# motherboard_rev0.net
KiCad netlist of a schematic drawn in EAGLE
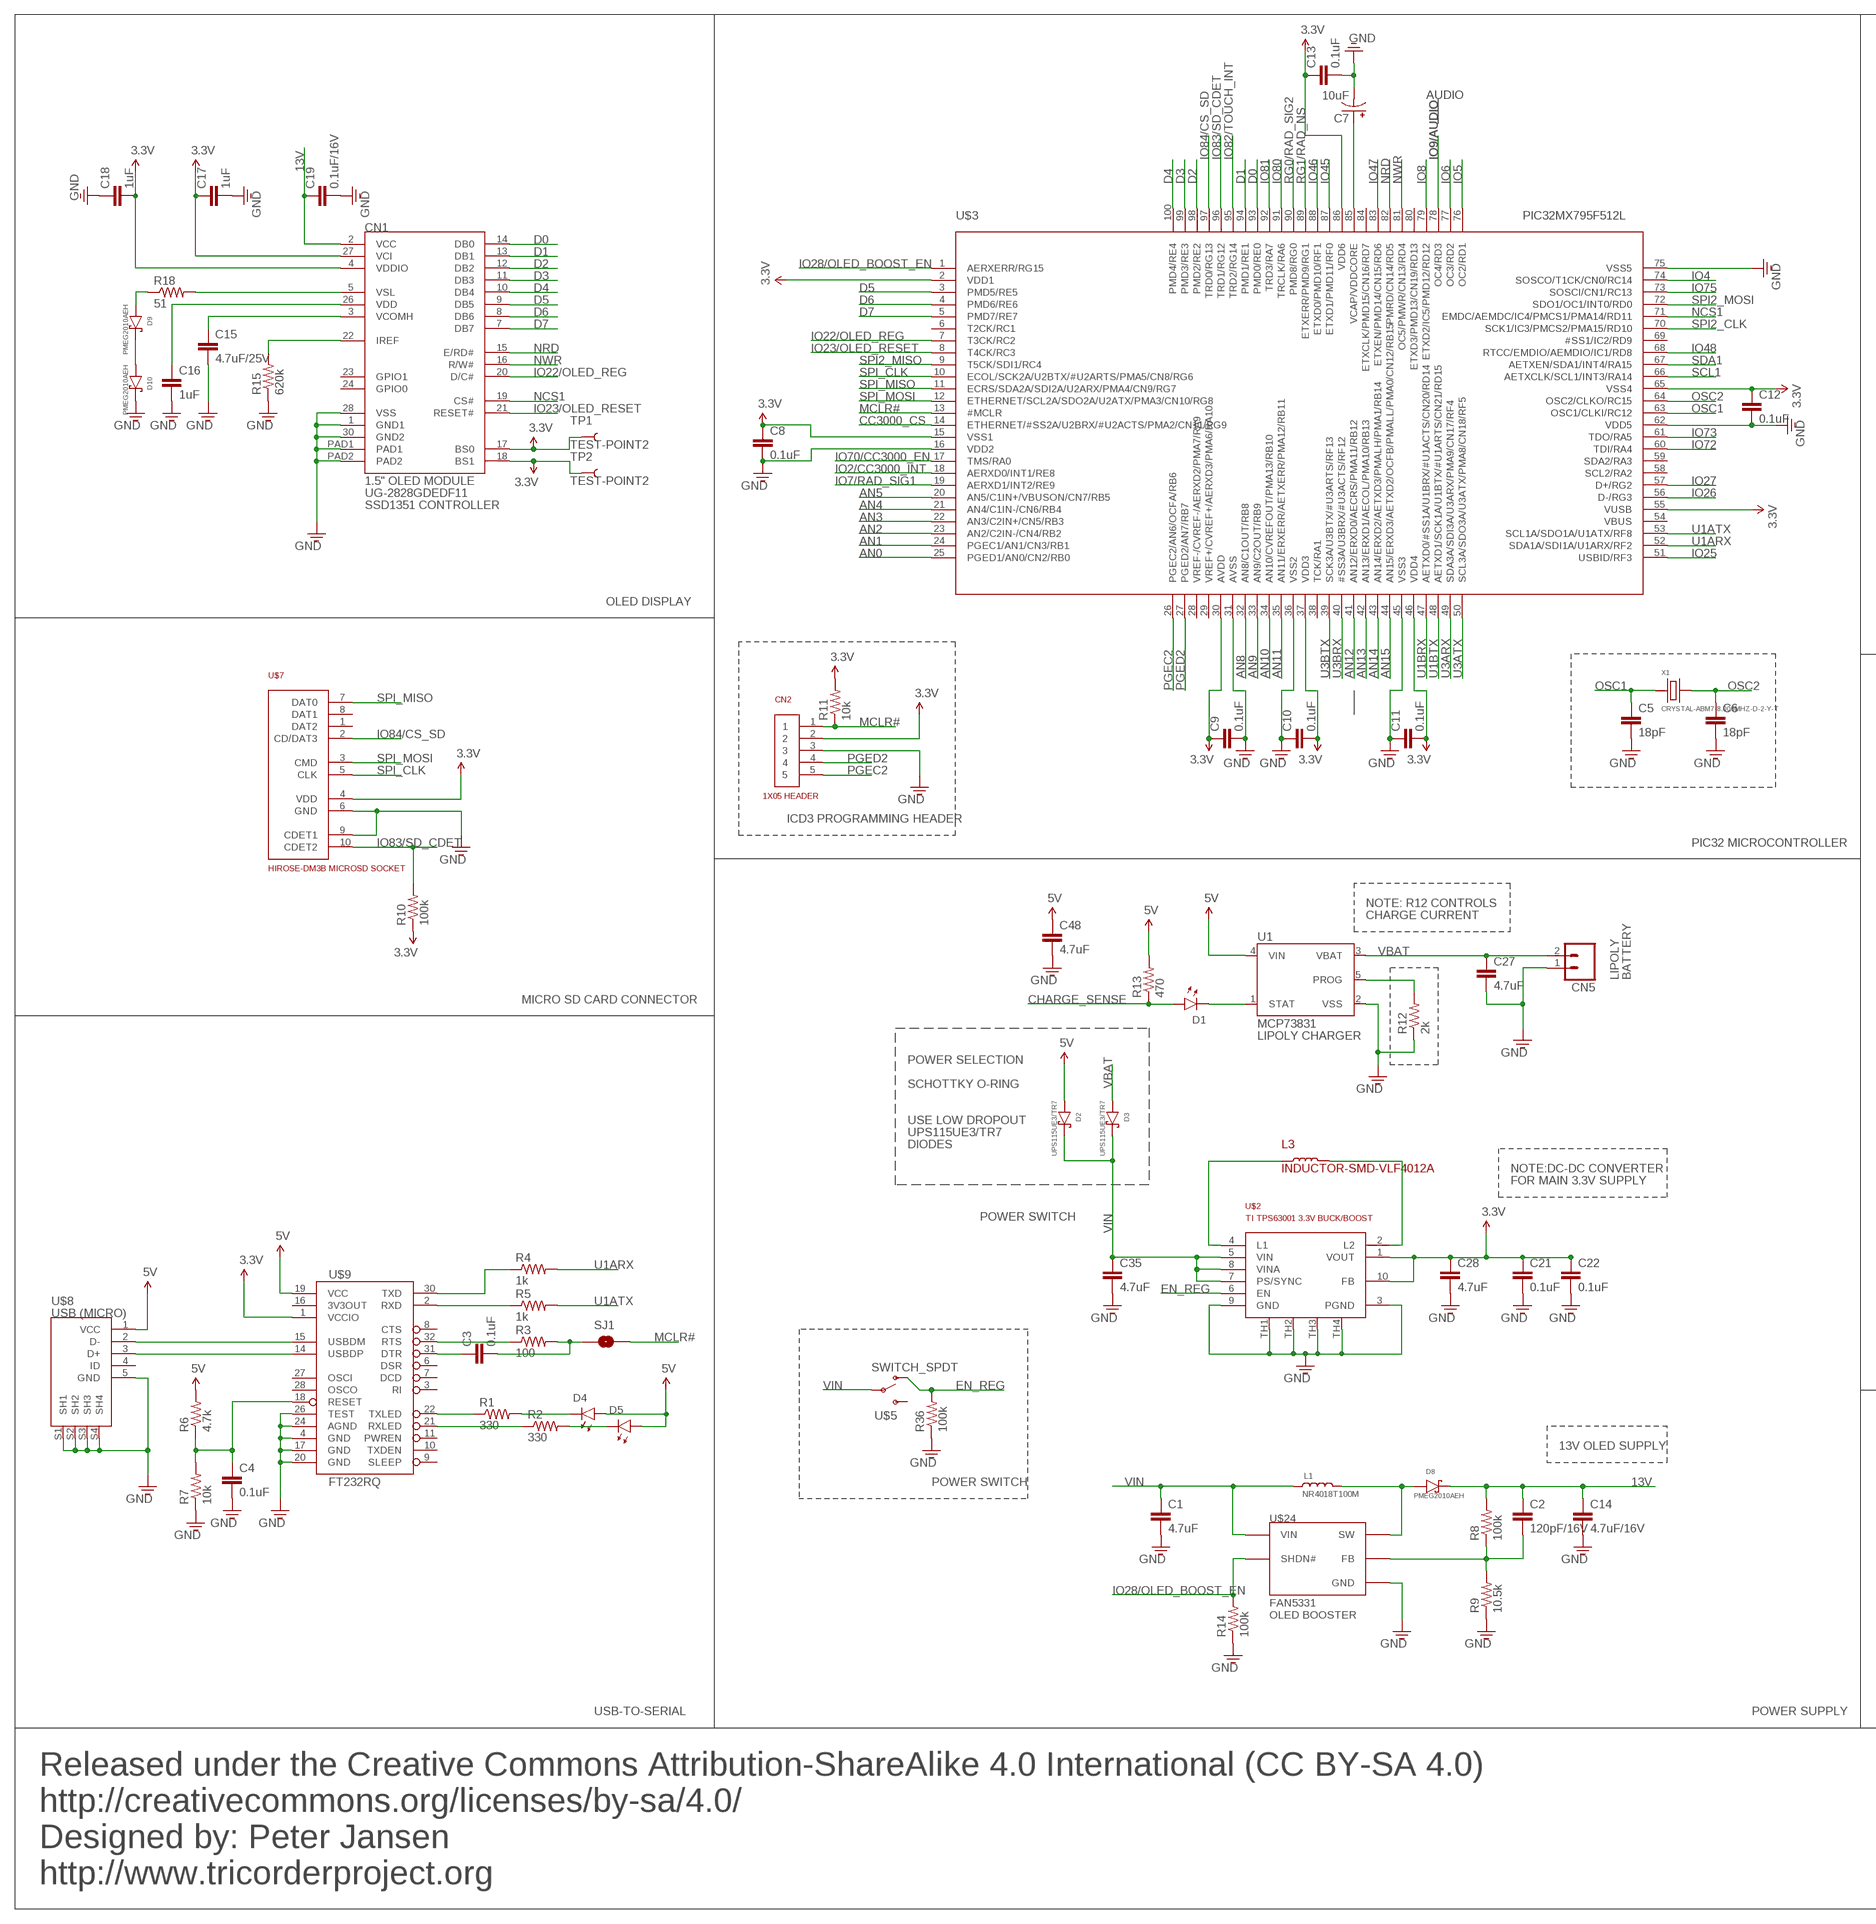
[diagram p0: schematic, sheet 1, part 1 of 2]
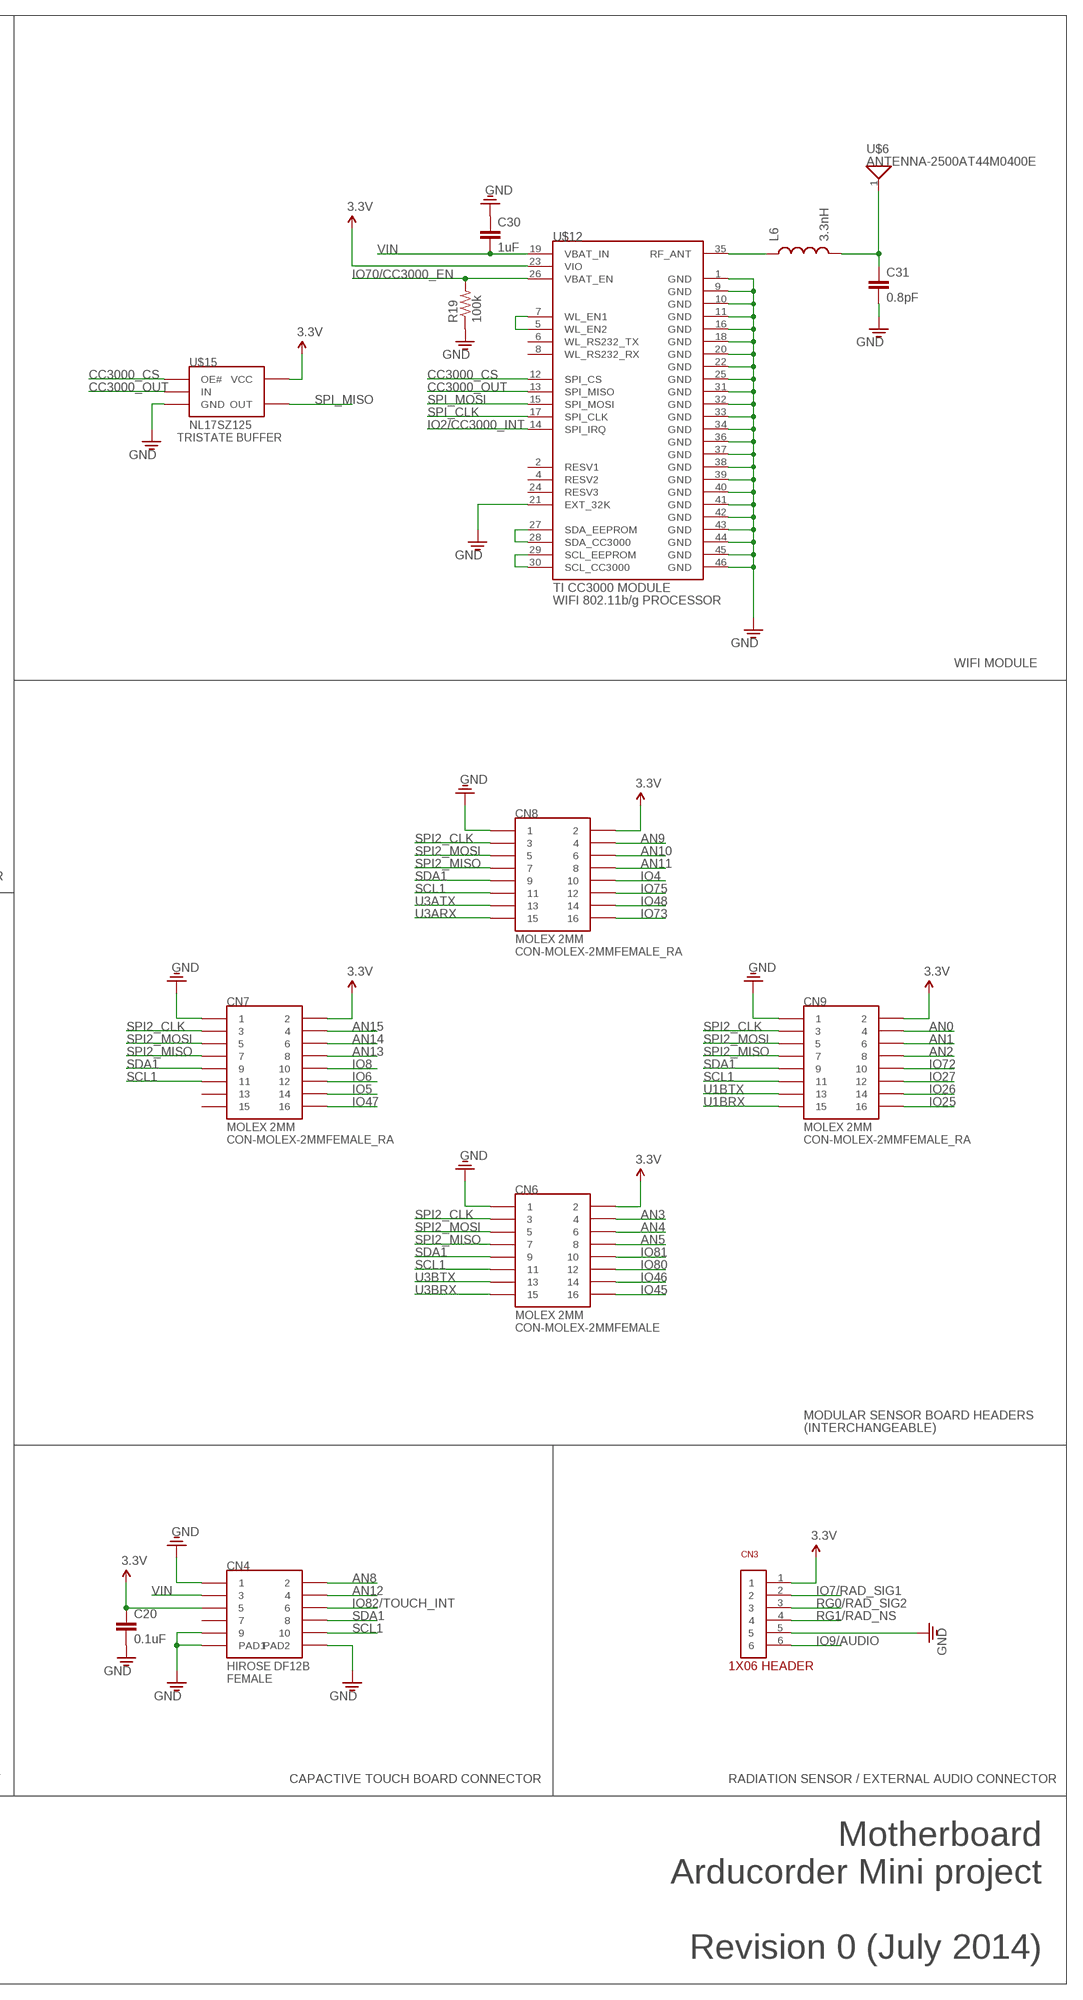
[diagram p1: schematic, sheet 1, part 2 of 2]

(export (version "E")
  (design (tool "Eeschema 10.0.6"))
  (components
    (comp (ref "C1")
      (value "4.7uF")
      (footprint "eagle-import:0603")
      (libsource (lib "eagle-import") (part "CAP0603"))
    )
    (comp (ref "C2")
      (value "120pF/16V")
      (footprint "eagle-import:0603")
      (libsource (lib "eagle-import") (part "notes_mark5a1_CAP0603"))
    )
    (comp (ref "C3")
      (value "0.1uF")
      (footprint "eagle-import:0603")
      (libsource (lib "eagle-import") (part "CAP0603"))
    )
    (comp (ref "C4")
      (value "0.1uF")
      (footprint "eagle-import:0603")
      (libsource (lib "eagle-import") (part "CAP0603"))
    )
    (comp (ref "C5")
      (value "18pF")
      (footprint "eagle-import:0603")
      (libsource (lib "eagle-import") (part "CAP0603"))
    )
    (comp (ref "C6")
      (value "18pF")
      (footprint "eagle-import:0603")
      (libsource (lib "eagle-import") (part "CAP0603"))
    )
    (comp (ref "C7")
      (value "10uF")
      (footprint "eagle-import:EIA3216")
      (libsource (lib "eagle-import") (part "CAP_POL1206"))
    )
    (comp (ref "C8")
      (value "0.1uF")
      (footprint "eagle-import:0603")
      (libsource (lib "eagle-import") (part "CAP0603"))
    )
    (comp (ref "C9")
      (value "0.1uF")
      (footprint "eagle-import:0603")
      (libsource (lib "eagle-import") (part "CAP0603"))
    )
    (comp (ref "C10")
      (value "0.1uF")
      (footprint "eagle-import:0603")
      (libsource (lib "eagle-import") (part "CAP0603"))
    )
    (comp (ref "C11")
      (value "0.1uF")
      (footprint "eagle-import:0603")
      (libsource (lib "eagle-import") (part "CAP0603"))
    )
    (comp (ref "C12")
      (value "0.1uF")
      (footprint "eagle-import:0603")
      (libsource (lib "eagle-import") (part "CAP0603"))
    )
    (comp (ref "C13")
      (value "0.1uF")
      (footprint "eagle-import:0603")
      (libsource (lib "eagle-import") (part "CAP0603"))
    )
    (comp (ref "C14")
      (value "4.7uF/16V")
      (footprint "eagle-import:0603")
      (libsource (lib "eagle-import") (part "CAP0603"))
    )
    (comp (ref "C15")
      (value "4.7uF/25V")
      (footprint "eagle-import:0603")
      (libsource (lib "eagle-import") (part "CAP0603"))
    )
    (comp (ref "C16")
      (value "1uF")
      (footprint "eagle-import:0603")
      (libsource (lib "eagle-import") (part "CAP0603"))
    )
    (comp (ref "C17")
      (value "1uF")
      (footprint "eagle-import:0603")
      (libsource (lib "eagle-import") (part "CAP0603"))
    )
    (comp (ref "C18")
      (value "1uF")
      (footprint "eagle-import:0603")
      (libsource (lib "eagle-import") (part "CAP0603"))
    )
    (comp (ref "C19")
      (value "0.1uF/16V")
      (footprint "eagle-import:0603")
      (libsource (lib "eagle-import") (part "CAP0603"))
    )
    (comp (ref "C20")
      (value "0.1uF")
      (footprint "eagle-import:0603")
      (libsource (lib "eagle-import") (part "CAP0603"))
    )
    (comp (ref "C21")
      (value "0.1uF")
      (footprint "eagle-import:0603")
      (libsource (lib "eagle-import") (part "CAP0603"))
    )
    (comp (ref "C22")
      (value "0.1uF")
      (footprint "eagle-import:0603")
      (libsource (lib "eagle-import") (part "CAP0603"))
    )
    (comp (ref "C27")
      (value "4.7uF")
      (footprint "eagle-import:0603")
      (libsource (lib "eagle-import") (part "CAP0603"))
    )
    (comp (ref "C28")
      (value "4.7uF")
      (footprint "eagle-import:0603")
      (libsource (lib "eagle-import") (part "CAP0603"))
    )
    (comp (ref "C30")
      (value "1uF")
      (footprint "eagle-import:0603")
      (libsource (lib "eagle-import") (part "CAP0603"))
    )
    (comp (ref "C31")
      (value "0.8pF")
      (footprint "eagle-import:C0402")
      (libsource (lib "eagle-import") (part "CAP0402"))
    )
    (comp (ref "C35")
      (value "4.7uF")
      (footprint "eagle-import:0603")
      (libsource (lib "eagle-import") (part "CAP0603"))
    )
    (comp (ref "C48")
      (value "4.7uF")
      (footprint "eagle-import:0603")
      (libsource (lib "eagle-import") (part "CAP0603"))
    )
    (comp (ref "CN1")
      (value "UG-2828GDEDF11-1.5OLED")
      (footprint "eagle-import:XF2M-3015-1A-1.5LCD")
      (libsource (lib "eagle-import") (part "UG-2828GDEDF11-1.5OLED"))
    )
    (comp (ref "CN2")
      (value "1X05")
      (footprint "eagle-import:1X05")
      (libsource (lib "eagle-import") (part "1X05"))
    )
    (comp (ref "CN3")
      (value "1X06")
      (footprint "eagle-import:1X06")
      (libsource (lib "eagle-import") (part "1X06"))
    )
    (comp (ref "CN4")
      (value "FEMALE")
      (footprint "eagle-import:DF12B(3.0)-10DP-0.5V(86)")
      (libsource (lib "eagle-import") (part "CON-HIROSE-DF12FEMALE"))
    )
    (comp (ref "CN5")
      (value "M02-JST-2MM-SMT")
      (footprint "eagle-import:JST-2-SMD")
      (libsource (lib "eagle-import") (part "M02-JST-2MM-SMT"))
    )
    (comp (ref "CN6")
      (value "CON-MOLEX-2MMFEMALE")
      (footprint "eagle-import:MOLEX-0791091007")
      (libsource (lib "eagle-import") (part "CON-MOLEX-2MMFEMALE"))
    )
    (comp (ref "CN7")
      (value "CON-MOLEX-2MMFEMALE_RA")
      (footprint "eagle-import:MOLEX-87368-1624")
      (libsource (lib "eagle-import") (part "CON-MOLEX-2MMFEMALE_RA"))
    )
    (comp (ref "CN8")
      (value "CON-MOLEX-2MMFEMALE_RA")
      (footprint "eagle-import:MOLEX-87368-1624")
      (libsource (lib "eagle-import") (part "CON-MOLEX-2MMFEMALE_RA"))
    )
    (comp (ref "CN9")
      (value "CON-MOLEX-2MMFEMALE_RA")
      (footprint "eagle-import:MOLEX-87368-1624")
      (libsource (lib "eagle-import") (part "CON-MOLEX-2MMFEMALE_RA"))
    )
    (comp (ref "D1")
      (value "0605-LED")
      (footprint "eagle-import:0603-LED")
      (libsource (lib "eagle-import") (part "0605-LED"))
    )
    (comp (ref "D2")
      (value "UPS115UE3/TR7")
      (footprint "eagle-import:DO-214BA")
      (libsource (lib "eagle-import") (part "DIODE-SCHOTTKY"))
    )
    (comp (ref "D3")
      (value "UPS115UE3/TR7")
      (footprint "eagle-import:DO-214BA")
      (libsource (lib "eagle-import") (part "DIODE-SCHOTTKY"))
    )
    (comp (ref "D4")
      (value "0605-LED")
      (footprint "eagle-import:0603-LED")
      (libsource (lib "eagle-import") (part "0605-LED"))
    )
    (comp (ref "D5")
      (value "0605-LED")
      (footprint "eagle-import:0603-LED")
      (libsource (lib "eagle-import") (part "0605-LED"))
    )
    (comp (ref "D8")
      (value "PMEG2010AEH")
      (footprint "eagle-import:SOD123F")
      (libsource (lib "eagle-import") (part "DIODE-SCHOTTKYSOD123F"))
    )
    (comp (ref "D9")
      (value "PMEG2010AEH")
      (footprint "eagle-import:SOD123F")
      (libsource (lib "eagle-import") (part "DIODE-SCHOTTKYSOD123F"))
    )
    (comp (ref "D10")
      (value "PMEG2010AEH")
      (footprint "eagle-import:SOD123F")
      (libsource (lib "eagle-import") (part "DIODE-SCHOTTKYSOD123F"))
    )
    (comp (ref "L1")
      (value "NR4018T100M")
      (footprint "eagle-import:NR4018T100M")
      (libsource (lib "eagle-import") (part "INDUCTORNR4018T100M"))
    )
    (comp (ref "L3")
      (value "INDUCTOR-SMD-VLF4012A")
      (footprint "eagle-import:VLF4012A")
      (libsource (lib "eagle-import") (part "INDUCTOR-SMD-VLF4012A"))
    )
    (comp (ref "L6")
      (value "3.3nH")
      (footprint "eagle-import:C0402")
      (libsource (lib "eagle-import") (part "INDUCTOR0402"))
    )
    (comp (ref "R1")
      (value "330")
      (footprint "eagle-import:0603")
      (libsource (lib "eagle-import") (part "RESISTOR0603"))
    )
    (comp (ref "R2")
      (value "330")
      (footprint "eagle-import:0603")
      (libsource (lib "eagle-import") (part "RESISTOR0603"))
    )
    (comp (ref "R3")
      (value "100")
      (footprint "eagle-import:0603")
      (libsource (lib "eagle-import") (part "RESISTOR0603"))
    )
    (comp (ref "R4")
      (value "1k")
      (footprint "eagle-import:0603")
      (libsource (lib "eagle-import") (part "RESISTOR0603"))
    )
    (comp (ref "R5")
      (value "1k")
      (footprint "eagle-import:0603")
      (libsource (lib "eagle-import") (part "RESISTOR0603"))
    )
    (comp (ref "R6")
      (value "4.7k")
      (footprint "eagle-import:0603")
      (libsource (lib "eagle-import") (part "RESISTOR0603"))
    )
    (comp (ref "R7")
      (value "10k")
      (footprint "eagle-import:0603")
      (libsource (lib "eagle-import") (part "RESISTOR0603"))
    )
    (comp (ref "R8")
      (value "100k")
      (footprint "eagle-import:0603")
      (libsource (lib "eagle-import") (part "notes_mark5a1_RESISTOR0603"))
    )
    (comp (ref "R9")
      (value "10.5k")
      (footprint "eagle-import:0603")
      (libsource (lib "eagle-import") (part "notes_mark5a1_RESISTOR0603"))
    )
    (comp (ref "R10")
      (value "100k")
      (footprint "eagle-import:0603")
      (libsource (lib "eagle-import") (part "RESISTOR0603"))
    )
    (comp (ref "R11")
      (value "10k")
      (footprint "eagle-import:0603")
      (libsource (lib "eagle-import") (part "RESISTOR0603"))
    )
    (comp (ref "R12")
      (value "2k")
      (footprint "eagle-import:0603")
      (libsource (lib "eagle-import") (part "RESISTOR0603"))
    )
    (comp (ref "R13")
      (value "470")
      (footprint "eagle-import:0603")
      (libsource (lib "eagle-import") (part "RESISTOR0603"))
    )
    (comp (ref "R14")
      (value "100k")
      (footprint "eagle-import:0603")
      (libsource (lib "eagle-import") (part "notes_mark5a1_RESISTOR0603"))
    )
    (comp (ref "R15")
      (value "620k")
      (footprint "eagle-import:0603")
      (libsource (lib "eagle-import") (part "notes_mark5a1_RESISTOR0603"))
    )
    (comp (ref "R18")
      (value "51")
      (footprint "eagle-import:0603")
      (libsource (lib "eagle-import") (part "notes_mark5a1_RESISTOR0603"))
    )
    (comp (ref "R19")
      (value "100k")
      (footprint "eagle-import:0603")
      (libsource (lib "eagle-import") (part "notes_mark5a1_RESISTOR0603"))
    )
    (comp (ref "R36")
      (value "100k")
      (footprint "eagle-import:0603")
      (libsource (lib "eagle-import") (part "RESISTOR0603"))
    )
    (comp (ref "SJ1")
      (value "SOLDERJUMPERTRACE")
      (footprint "eagle-import:SJ_2S-TRACE")
      (libsource (lib "eagle-import") (part "SOLDERJUMPERTRACE"))
    )
    (comp (ref "TP1")
      (value "TEST-POINT2")
      (footprint "eagle-import:PAD.02X.02")
      (libsource (lib "eagle-import") (part "TEST-POINT2"))
    )
    (comp (ref "TP2")
      (value "TEST-POINT2")
      (footprint "eagle-import:PAD.02X.02")
      (libsource (lib "eagle-import") (part "TEST-POINT2"))
    )
    (comp (ref "U$2")
      (value "TI-TPS63001-3.3V-BUCKBOOST")
      (footprint "eagle-import:TPS63001")
      (libsource (lib "eagle-import") (part "TI-TPS63001-3.3V-BUCKBOOST"))
    )
    (comp (ref "U$3")
      (value "PIC32MX795F512L-80I/PF")
      (footprint "eagle-import:SQFP-S-14X14-100")
      (libsource (lib "eagle-import") (part "PIC32MX795F512L-80I/PF"))
    )
    (comp (ref "U$5")
      (value "SWITCH_SPDT")
      (footprint "eagle-import:KPS-1290")
      (libsource (lib "eagle-import") (part "SWITCH_SPDT"))
    )
    (comp (ref "U$6")
      (value "ANTENNA-2500AT44M0400E")
      (footprint "eagle-import:ANT-2500AT44M0400E")
      (libsource (lib "eagle-import") (part "ANTENNA-2500AT44M0400E"))
    )
    (comp (ref "U$7")
      (value "CON-HIROSE-DM3B-MICROSD")
      (footprint "eagle-import:CON-HIROSE-DM3B-MICROSD")
      (libsource (lib "eagle-import") (part "CON-HIROSE-DM3B-MICROSD"))
    )
    (comp (ref "U$8")
      (value "USB-MICROB")
      (footprint "eagle-import:FCI-10104110-0001LF")
      (libsource (lib "eagle-import") (part "USB-MICROB"))
    )
    (comp (ref "U$9")
      (value "FT232RQ")
      (footprint "eagle-import:QFN-32")
      (libsource (lib "eagle-import") (part "FT232RQ"))
    )
    (comp (ref "U$12")
      (value "CC3000")
      (footprint "eagle-import:CC3000")
      (libsource (lib "eagle-import") (part "CC3000"))
    )
    (comp (ref "U$15")
      (value "BUFFER-NL17SZ125")
      (footprint "eagle-import:TSOP-5")
      (libsource (lib "eagle-import") (part "BUFFER-NL17SZ125"))
    )
    (comp (ref "U$24")
      (value "FAN5331-BOOST")
      (footprint "eagle-import:TSOP-5")
      (libsource (lib "eagle-import") (part "FAN5331-BOOST"))
    )
    (comp (ref "U1")
      (value "MCP73831")
      (footprint "eagle-import:SOT23-5")
      (libsource (lib "eagle-import") (part "MCP73831"))
    )
    (comp (ref "X1")
      (value "CRYSTAL-ABM7-8.000MHZ-D-2-Y-T")
      (footprint "eagle-import:CYRSTAL-6.0X3.5MM")
      (libsource (lib "eagle-import") (part "CRYSTAL-ABM7-8.000MHZ-D-2-Y-T"))
    )
  )
  (nets
    (net (code "1") (name "/13V") (class "Default")
      (node (ref "C14") (pin "1") (pinfunction "1_1") (pintype "passive"))
      (node (ref "C19") (pin "1") (pinfunction "1_1") (pintype "passive"))
      (node (ref "C2") (pin "1") (pinfunction "1_1") (pintype "passive"))
      (node (ref "CN1") (pin "2") (pinfunction "VCC_2") (pintype "bidirectional"))
      (node (ref "D8") (pin "1") (pinfunction "CATHODE_1") (pintype "bidirectional"))
      (node (ref "R8") (pin "2") (pinfunction "2_2") (pintype "passive"))
    )
    (net (code "2") (name "/AN0") (class "Default")
      (node (ref "CN9") (pin "4") (pinfunction "4_4") (pintype "bidirectional"))
      (node (ref "U$3") (pin "25") (pinfunction "PGED1/AN0/CN2/RB0_25") (pintype "bidirectional"))
    )
    (net (code "3") (name "/AN1") (class "Default")
      (node (ref "CN9") (pin "6") (pinfunction "6_6") (pintype "bidirectional"))
      (node (ref "U$3") (pin "24") (pinfunction "PGEC1/AN1/CN3/RB1_24") (pintype "bidirectional"))
    )
    (net (code "4") (name "/AN2") (class "Default")
      (node (ref "CN9") (pin "8") (pinfunction "8_8") (pintype "bidirectional"))
      (node (ref "U$3") (pin "23") (pinfunction "AN2/C2IN-/CN4/RB2_23") (pintype "bidirectional"))
    )
    (net (code "5") (name "/AN3") (class "Default")
      (node (ref "CN6") (pin "4") (pinfunction "4_4") (pintype "bidirectional"))
      (node (ref "U$3") (pin "22") (pinfunction "AN3/C2IN+/CN5/RB3_22") (pintype "bidirectional"))
    )
    (net (code "6") (name "/AN4") (class "Default")
      (node (ref "CN6") (pin "6") (pinfunction "6_6") (pintype "bidirectional"))
      (node (ref "U$3") (pin "21") (pinfunction "AN4/C1IN-/CN6/RB4_21") (pintype "bidirectional"))
    )
    (net (code "7") (name "/AN5") (class "Default")
      (node (ref "CN6") (pin "8") (pinfunction "8_8") (pintype "bidirectional"))
      (node (ref "U$3") (pin "20") (pinfunction "AN5/C1IN+/VBUSON/CN7/RB5_20") (pintype "bidirectional"))
    )
    (net (code "8") (name "/AN8") (class "Default")
      (node (ref "CN4") (pin "2") (pinfunction "2_2") (pintype "bidirectional"))
      (node (ref "U$3") (pin "32") (pinfunction "AN8/C1OUT/RB8_32") (pintype "bidirectional"))
    )
    (net (code "9") (name "/AN9") (class "Default")
      (node (ref "CN8") (pin "4") (pinfunction "4_4") (pintype "bidirectional"))
      (node (ref "U$3") (pin "33") (pinfunction "AN9/C2OUT/RB9_33") (pintype "bidirectional"))
    )
    (net (code "10") (name "/AN10") (class "Default")
      (node (ref "CN8") (pin "6") (pinfunction "6_6") (pintype "bidirectional"))
      (node (ref "U$3") (pin "34") (pinfunction "AN10/CVREFOUT/PMA13/RB10_34") (pintype "bidirectional"))
    )
    (net (code "11") (name "/AN11") (class "Default")
      (node (ref "CN8") (pin "8") (pinfunction "8_8") (pintype "bidirectional"))
      (node (ref "U$3") (pin "35") (pinfunction "AN11/ERXERR/AETXERR/PMA12/RB11_35") (pintype "bidirectional"))
    )
    (net (code "12") (name "/AN12") (class "Default")
      (node (ref "CN4") (pin "4") (pinfunction "4_4") (pintype "bidirectional"))
      (node (ref "U$3") (pin "41") (pinfunction "AN12/ERXD0/AECRS/PMA11/RB12_41") (pintype "bidirectional"))
    )
    (net (code "13") (name "/AN13") (class "Default")
      (node (ref "CN7") (pin "8") (pinfunction "8_8") (pintype "bidirectional"))
      (node (ref "U$3") (pin "42") (pinfunction "AN13/ERXD1/AECOL/PMA10/RB13_42") (pintype "bidirectional"))
    )
    (net (code "14") (name "/AN14") (class "Default")
      (node (ref "CN7") (pin "6") (pinfunction "6_6") (pintype "bidirectional"))
      (node (ref "U$3") (pin "43") (pinfunction "AN14/ERXD2/AETXD3/PMALH/PMA1/RB14_43") (pintype "bidirectional"))
    )
    (net (code "15") (name "/AN15") (class "Default")
      (node (ref "CN7") (pin "4") (pinfunction "4_4") (pintype "bidirectional"))
      (node (ref "U$3") (pin "44") (pinfunction "AN15/ERXD3/AETXD2/OCFB/PMALL/PMA0/CN12/RB15_44") (pintype "bidirectional"))
    )
    (net (code "16") (name "/CC3000_CS") (class "Default")
      (node (ref "U$12") (pin "12") (pinfunction "SPI_CS_12") (pintype "bidirectional"))
      (node (ref "U$15") (pin "1") (pinfunction "OE#_1") (pintype "bidirectional"))
      (node (ref "U$3") (pin "14") (pinfunction "ETHERNET/#SS2A/U2BRX/#U2ACTS/PMA2/CN11/RG9_14") (pintype "bidirectional"))
    )
    (net (code "17") (name "/CC3000_OUT") (class "Default")
      (node (ref "U$12") (pin "13") (pinfunction "SPI_MISO_13") (pintype "bidirectional"))
      (node (ref "U$15") (pin "2") (pinfunction "IN_2") (pintype "bidirectional"))
    )
    (net (code "18") (name "/CHARGE_SENSE") (class "Default")
      (node (ref "D1") (pin "ANODE") (pinfunction "ANODE_ANODE") (pintype "bidirectional"))
      (node (ref "R13") (pin "1") (pinfunction "1_1") (pintype "passive"))
    )
    (net (code "19") (name "/D0") (class "Default")
      (node (ref "CN1") (pin "14") (pinfunction "DB0_14") (pintype "bidirectional"))
      (node (ref "U$3") (pin "93") (pinfunction "PMD0/RE0_93") (pintype "bidirectional"))
    )
    (net (code "20") (name "/D1") (class "Default")
      (node (ref "CN1") (pin "13") (pinfunction "DB1_13") (pintype "bidirectional"))
      (node (ref "U$3") (pin "94") (pinfunction "PMD1/RE1_94") (pintype "bidirectional"))
    )
    (net (code "21") (name "/D2") (class "Default")
      (node (ref "CN1") (pin "12") (pinfunction "DB2_12") (pintype "bidirectional"))
      (node (ref "U$3") (pin "98") (pinfunction "PMD2/RE2_98") (pintype "bidirectional"))
    )
    (net (code "22") (name "/D3") (class "Default")
      (node (ref "CN1") (pin "11") (pinfunction "DB3_11") (pintype "bidirectional"))
      (node (ref "U$3") (pin "99") (pinfunction "PMD3/RE3_99") (pintype "bidirectional"))
    )
    (net (code "23") (name "/D4") (class "Default")
      (node (ref "CN1") (pin "10") (pinfunction "DB4_10") (pintype "bidirectional"))
      (node (ref "U$3") (pin "100") (pinfunction "PMD4/RE4_100") (pintype "bidirectional"))
    )
    (net (code "24") (name "/D5") (class "Default")
      (node (ref "CN1") (pin "9") (pinfunction "DB5_9") (pintype "bidirectional"))
      (node (ref "U$3") (pin "3") (pinfunction "PMD5/RE5_3") (pintype "bidirectional"))
    )
    (net (code "25") (name "/D6") (class "Default")
      (node (ref "CN1") (pin "8") (pinfunction "DB6_8") (pintype "bidirectional"))
      (node (ref "U$3") (pin "4") (pinfunction "PMD6/RE6_4") (pintype "bidirectional"))
    )
    (net (code "26") (name "/D7") (class "Default")
      (node (ref "CN1") (pin "7") (pinfunction "DB7_7") (pintype "bidirectional"))
      (node (ref "U$3") (pin "5") (pinfunction "PMD7/RE7_5") (pintype "bidirectional"))
    )
    (net (code "27") (name "/EN_REG") (class "Default")
      (node (ref "R36") (pin "2") (pinfunction "2_2") (pintype "passive"))
      (node (ref "U$2") (pin "6") (pinfunction "EN_6") (pintype "bidirectional"))
      (node (ref "U$5") (pin "O") (pinfunction "O_O") (pintype "passive"))
    )
    (net (code "28") (name "/IO2{slash}CC3000_INT") (class "Default")
      (node (ref "U$12") (pin "14") (pinfunction "SPI_IRQ_14") (pintype "bidirectional"))
      (node (ref "U$3") (pin "18") (pinfunction "AERXD0/INT1/RE8_18") (pintype "bidirectional"))
    )
    (net (code "29") (name "/IO4") (class "Default")
      (node (ref "CN8") (pin "10") (pinfunction "10_10") (pintype "bidirectional"))
      (node (ref "U$3") (pin "74") (pinfunction "SOSCO/T1CK/CN0/RC14_74") (pintype "bidirectional"))
    )
    (net (code "30") (name "/IO5") (class "Default")
      (node (ref "CN7") (pin "14") (pinfunction "14_14") (pintype "bidirectional"))
      (node (ref "U$3") (pin "76") (pinfunction "OC2/RD1_76") (pintype "bidirectional"))
    )
    (net (code "31") (name "/IO6") (class "Default")
      (node (ref "CN7") (pin "12") (pinfunction "12_12") (pintype "bidirectional"))
      (node (ref "U$3") (pin "77") (pinfunction "OC3/RD2_77") (pintype "bidirectional"))
    )
    (net (code "32") (name "/IO7{slash}RAD_SIG1") (class "Default")
      (node (ref "CN3") (pin "2") (pinfunction "2_2") (pintype "bidirectional"))
      (node (ref "U$3") (pin "19") (pinfunction "AERXD1/INT2/RE9_19") (pintype "bidirectional"))
    )
    (net (code "33") (name "/IO8") (class "Default")
      (node (ref "CN7") (pin "10") (pinfunction "10_10") (pintype "bidirectional"))
      (node (ref "U$3") (pin "79") (pinfunction "ETXD2/IC5/PMD12/RD12_79") (pintype "bidirectional"))
    )
    (net (code "34") (name "/IO9{slash}AUDIO") (class "Default")
      (node (ref "CN3") (pin "6") (pinfunction "6_6") (pintype "bidirectional"))
      (node (ref "U$3") (pin "78") (pinfunction "OC4/RD3_78") (pintype "bidirectional"))
    )
    (net (code "35") (name "/IO22{slash}OLED_REG") (class "Default")
      (node (ref "CN1") (pin "20") (pinfunction "D/C#_20") (pintype "bidirectional"))
      (node (ref "U$3") (pin "7") (pinfunction "T3CK/RC2_7") (pintype "bidirectional"))
    )
    (net (code "36") (name "/IO23{slash}OLED_RESET") (class "Default")
      (node (ref "CN1") (pin "21") (pinfunction "RESET#_21") (pintype "bidirectional"))
      (node (ref "U$3") (pin "8") (pinfunction "T4CK/RC3_8") (pintype "bidirectional"))
    )
    (net (code "37") (name "/IO25") (class "Default")
      (node (ref "CN9") (pin "16") (pinfunction "16_16") (pintype "bidirectional"))
      (node (ref "U$3") (pin "51") (pinfunction "USBID/RF3_51") (pintype "bidirectional"))
    )
    (net (code "38") (name "/IO26") (class "Default")
      (node (ref "CN9") (pin "14") (pinfunction "14_14") (pintype "bidirectional"))
      (node (ref "U$3") (pin "56") (pinfunction "D-/RG3_56") (pintype "bidirectional"))
    )
    (net (code "39") (name "/IO27") (class "Default")
      (node (ref "CN9") (pin "12") (pinfunction "12_12") (pintype "bidirectional"))
      (node (ref "U$3") (pin "57") (pinfunction "D+/RG2_57") (pintype "bidirectional"))
    )
    (net (code "40") (name "/IO28{slash}OLED_BOOST_EN") (class "Default")
      (node (ref "R14") (pin "2") (pinfunction "2_2") (pintype "passive"))
      (node (ref "U$24") (pin "4") (pinfunction "SHDN#_4") (pintype "bidirectional"))
      (node (ref "U$3") (pin "1") (pinfunction "AERXERR/RG15_1") (pintype "bidirectional"))
    )
    (net (code "41") (name "/IO45") (class "Default")
      (node (ref "CN6") (pin "16") (pinfunction "16_16") (pintype "bidirectional"))
      (node (ref "U$3") (pin "87") (pinfunction "ETXD1/PMD11/RF0_87") (pintype "bidirectional"))
    )
    (net (code "42") (name "/IO46") (class "Default")
      (node (ref "CN6") (pin "14") (pinfunction "14_14") (pintype "bidirectional"))
      (node (ref "U$3") (pin "88") (pinfunction "ETXD0/PMD10/RF1_88") (pintype "bidirectional"))
    )
    (net (code "43") (name "/IO47") (class "Default")
      (node (ref "CN7") (pin "16") (pinfunction "16_16") (pintype "bidirectional"))
      (node (ref "U$3") (pin "83") (pinfunction "ETXEN/PMD14/CN15/RD6_83") (pintype "bidirectional"))
    )
    (net (code "44") (name "/IO48") (class "Default")
      (node (ref "CN8") (pin "14") (pinfunction "14_14") (pintype "bidirectional"))
      (node (ref "U$3") (pin "68") (pinfunction "RTCC/EMDIO/AEMDIO/IC1/RD8_68") (pintype "bidirectional"))
    )
    (net (code "45") (name "/IO70{slash}CC3000_EN") (class "Default")
      (node (ref "R19") (pin "2") (pinfunction "2_2") (pintype "passive"))
      (node (ref "U$12") (pin "26") (pinfunction "VBAT_EN_26") (pintype "bidirectional"))
      (node (ref "U$3") (pin "17") (pinfunction "TMS/RA0_17") (pintype "bidirectional"))
    )
    (net (code "46") (name "/IO72") (class "Default")
      (node (ref "CN9") (pin "10") (pinfunction "10_10") (pintype "bidirectional"))
      (node (ref "U$3") (pin "60") (pinfunction "TDI/RA4_60") (pintype "bidirectional"))
    )
    (net (code "47") (name "/IO73") (class "Default")
      (node (ref "CN8") (pin "16") (pinfunction "16_16") (pintype "bidirectional"))
      (node (ref "U$3") (pin "61") (pinfunction "TDO/RA5_61") (pintype "bidirectional"))
    )
    (net (code "48") (name "/IO75") (class "Default")
      (node (ref "CN8") (pin "12") (pinfunction "12_12") (pintype "bidirectional"))
      (node (ref "U$3") (pin "73") (pinfunction "SOSCI/CN1/RC13_73") (pintype "bidirectional"))
    )
    (net (code "49") (name "/IO80") (class "Default")
      (node (ref "CN6") (pin "12") (pinfunction "12_12") (pintype "bidirectional"))
      (node (ref "U$3") (pin "91") (pinfunction "TRCLK/RA6_91") (pintype "bidirectional"))
    )
    (net (code "50") (name "/IO81") (class "Default")
      (node (ref "CN6") (pin "10") (pinfunction "10_10") (pintype "bidirectional"))
      (node (ref "U$3") (pin "92") (pinfunction "TRD3/RA7_92") (pintype "bidirectional"))
    )
    (net (code "51") (name "/IO82{slash}TOUCH_INT") (class "Default")
      (node (ref "CN4") (pin "6") (pinfunction "6_6") (pintype "bidirectional"))
      (node (ref "U$3") (pin "95") (pinfunction "TRD2/RG14_95") (pintype "bidirectional"))
    )
    (net (code "52") (name "/IO83{slash}SD_CDET") (class "Default")
      (node (ref "R10") (pin "2") (pinfunction "2_2") (pintype "passive"))
      (node (ref "U$3") (pin "96") (pinfunction "TRD1/RG12_96") (pintype "bidirectional"))
      (node (ref "U$7") (pin "10") (pinfunction "CDET2_10") (pintype "bidirectional"))
    )
    (net (code "53") (name "/IO84{slash}CS_SD") (class "Default")
      (node (ref "U$3") (pin "97") (pinfunction "TRD0/RG13_97") (pintype "bidirectional"))
      (node (ref "U$7") (pin "2") (pinfunction "CD/DAT3_2") (pintype "bidirectional"))
    )
    (net (code "54") (name "/MCLR#") (class "Default")
      (node (ref "CN2") (pin "1") (pinfunction "1_1") (pintype "bidirectional"))
      (node (ref "R11") (pin "1") (pinfunction "1_1") (pintype "passive"))
      (node (ref "SJ1") (pin "2") (pinfunction "2_2") (pintype "passive"))
      (node (ref "U$3") (pin "13") (pinfunction "#MCLR_13") (pintype "bidirectional"))
    )
    (net (code "55") (name "/NCS1") (class "Default")
      (node (ref "CN1") (pin "19") (pinfunction "CS#_19") (pintype "bidirectional"))
      (node (ref "U$3") (pin "71") (pinfunction "EMDC/AEMDC/IC4/PMCS1/PMA14/RD11_71") (pintype "bidirectional"))
    )
    (net (code "56") (name "/NRD") (class "Default")
      (node (ref "CN1") (pin "15") (pinfunction "E/RD#_15") (pintype "bidirectional"))
      (node (ref "U$3") (pin "82") (pinfunction "PMRD/CN14/RD5_82") (pintype "bidirectional"))
    )
    (net (code "57") (name "/NWR") (class "Default")
      (node (ref "CN1") (pin "16") (pinfunction "R/W#_16") (pintype "bidirectional"))
      (node (ref "U$3") (pin "81") (pinfunction "OC5/PMWR/CN13/RD4_81") (pintype "bidirectional"))
    )
    (net (code "58") (name "/OSC1") (class "Default")
      (node (ref "C5") (pin "1") (pinfunction "1_1") (pintype "passive"))
      (node (ref "U$3") (pin "63") (pinfunction "OSC1/CLKI/RC12_63") (pintype "bidirectional"))
      (node (ref "X1") (pin "1") (pinfunction "P$1_1") (pintype "bidirectional"))
    )
    (net (code "59") (name "/OSC2") (class "Default")
      (node (ref "C6") (pin "1") (pinfunction "1_1") (pintype "passive"))
      (node (ref "U$3") (pin "64") (pinfunction "OSC2/CLKO/RC15_64") (pintype "bidirectional"))
      (node (ref "X1") (pin "2") (pinfunction "P$2_2") (pintype "bidirectional"))
    )
    (net (code "60") (name "/PGEC2") (class "Default")
      (node (ref "CN2") (pin "5") (pinfunction "5_5") (pintype "bidirectional"))
      (node (ref "U$3") (pin "26") (pinfunction "PGEC2/AN6/OCFA/RB6_26") (pintype "bidirectional"))
    )
    (net (code "61") (name "/PGED2") (class "Default")
      (node (ref "CN2") (pin "4") (pinfunction "4_4") (pintype "bidirectional"))
      (node (ref "U$3") (pin "27") (pinfunction "PGED2/AN7/RB7_27") (pintype "bidirectional"))
    )
    (net (code "62") (name "/RG0{slash}RAD_SIG2") (class "Default")
      (node (ref "CN3") (pin "3") (pinfunction "3_3") (pintype "bidirectional"))
      (node (ref "U$3") (pin "90") (pinfunction "PMD8/RG0_90") (pintype "bidirectional"))
    )
    (net (code "63") (name "/RG1{slash}RAD_NS") (class "Default")
      (node (ref "CN3") (pin "4") (pinfunction "4_4") (pintype "bidirectional"))
      (node (ref "U$3") (pin "89") (pinfunction "ETXERR/PMD9/RG1_89") (pintype "bidirectional"))
    )
    (net (code "64") (name "/SCL1") (class "Default")
      (node (ref "CN4") (pin "10") (pinfunction "10_10") (pintype "bidirectional"))
      (node (ref "CN6") (pin "11") (pinfunction "11_11") (pintype "bidirectional"))
      (node (ref "CN7") (pin "11") (pinfunction "11_11") (pintype "bidirectional"))
      (node (ref "CN8") (pin "11") (pinfunction "11_11") (pintype "bidirectional"))
      (node (ref "CN9") (pin "11") (pinfunction "11_11") (pintype "bidirectional"))
      (node (ref "U$3") (pin "66") (pinfunction "AETXCLK/SCL1/INT3/RA14_66") (pintype "bidirectional"))
    )
    (net (code "65") (name "/SDA1") (class "Default")
      (node (ref "CN4") (pin "8") (pinfunction "8_8") (pintype "bidirectional"))
      (node (ref "CN6") (pin "9") (pinfunction "9_9") (pintype "bidirectional"))
      (node (ref "CN7") (pin "9") (pinfunction "9_9") (pintype "bidirectional"))
      (node (ref "CN8") (pin "9") (pinfunction "9_9") (pintype "bidirectional"))
      (node (ref "CN9") (pin "9") (pinfunction "9_9") (pintype "bidirectional"))
      (node (ref "U$3") (pin "67") (pinfunction "AETXEN/SDA1/INT4/RA15_67") (pintype "bidirectional"))
    )
    (net (code "66") (name "/SPI2_CLK") (class "Default")
      (node (ref "CN6") (pin "3") (pinfunction "3_3") (pintype "bidirectional"))
      (node (ref "CN7") (pin "3") (pinfunction "3_3") (pintype "bidirectional"))
      (node (ref "CN8") (pin "3") (pinfunction "3_3") (pintype "bidirectional"))
      (node (ref "CN9") (pin "3") (pinfunction "3_3") (pintype "bidirectional"))
      (node (ref "U$3") (pin "70") (pinfunction "SCK1/IC3/PMCS2/PMA15/RD10_70") (pintype "bidirectional"))
    )
    (net (code "67") (name "/SPI2_MISO") (class "Default")
      (node (ref "CN6") (pin "7") (pinfunction "7_7") (pintype "bidirectional"))
      (node (ref "CN7") (pin "7") (pinfunction "7_7") (pintype "bidirectional"))
      (node (ref "CN8") (pin "7") (pinfunction "7_7") (pintype "bidirectional"))
      (node (ref "CN9") (pin "7") (pinfunction "7_7") (pintype "bidirectional"))
      (node (ref "U$3") (pin "9") (pinfunction "T5CK/SDI1/RC4_9") (pintype "bidirectional"))
    )
    (net (code "68") (name "/SPI2_MOSI") (class "Default")
      (node (ref "CN6") (pin "5") (pinfunction "5_5") (pintype "bidirectional"))
      (node (ref "CN7") (pin "5") (pinfunction "5_5") (pintype "bidirectional"))
      (node (ref "CN8") (pin "5") (pinfunction "5_5") (pintype "bidirectional"))
      (node (ref "CN9") (pin "5") (pinfunction "5_5") (pintype "bidirectional"))
      (node (ref "U$3") (pin "72") (pinfunction "SDO1/OC1/INT0/RD0_72") (pintype "bidirectional"))
    )
    (net (code "69") (name "/SPI_CLK") (class "Default")
      (node (ref "U$12") (pin "17") (pinfunction "SPI_CLK_17") (pintype "bidirectional"))
      (node (ref "U$3") (pin "10") (pinfunction "ECOL/SCK2A/U2BTX/#U2ARTS/PMA5/CN8/RG6_10") (pintype "bidirectional"))
      (node (ref "U$7") (pin "5") (pinfunction "CLK_5") (pintype "bidirectional"))
    )
    (net (code "70") (name "/SPI_MISO") (class "Default")
      (node (ref "U$15") (pin "4") (pinfunction "OUT_4") (pintype "bidirectional"))
      (node (ref "U$3") (pin "11") (pinfunction "ECRS/SDA2A/SDI2A/U2ARX/PMA4/CN9/RG7_11") (pintype "bidirectional"))
      (node (ref "U$7") (pin "7") (pinfunction "DAT0_7") (pintype "bidirectional"))
    )
    (net (code "71") (name "/SPI_MOSI") (class "Default")
      (node (ref "U$12") (pin "15") (pinfunction "SPI_MOSI_15") (pintype "bidirectional"))
      (node (ref "U$3") (pin "12") (pinfunction "ETHERNET/SCL2A/SDO2A/U2ATX/PMA3/CN10/RG8_12") (pintype "bidirectional"))
      (node (ref "U$7") (pin "3") (pinfunction "CMD_3") (pintype "bidirectional"))
    )
    (net (code "72") (name "/U1ARX") (class "Default")
      (node (ref "R4") (pin "2") (pinfunction "2_2") (pintype "passive"))
      (node (ref "U$3") (pin "52") (pinfunction "SDA1A/SDI1A/U1ARX/RF2_52") (pintype "bidirectional"))
    )
    (net (code "73") (name "/U1ATX") (class "Default")
      (node (ref "R5") (pin "2") (pinfunction "2_2") (pintype "passive"))
      (node (ref "U$3") (pin "53") (pinfunction "SCL1A/SDO1A/U1ATX/RF8_53") (pintype "bidirectional"))
    )
    (net (code "74") (name "/U1BRX") (class "Default")
      (node (ref "CN9") (pin "15") (pinfunction "15_15") (pintype "bidirectional"))
      (node (ref "U$3") (pin "47") (pinfunction "AETXD0/#SS1A/U1BRX/#U1ACTS/CN20/RD14_47") (pintype "bidirectional"))
    )
    (net (code "75") (name "/U1BTX") (class "Default")
      (node (ref "CN9") (pin "13") (pinfunction "13_13") (pintype "bidirectional"))
      (node (ref "U$3") (pin "48") (pinfunction "AETXD1/SCK1A/U1BTX/#U1ARTS/CN21/RD15_48") (pintype "bidirectional"))
    )
    (net (code "76") (name "/U3ARX") (class "Default")
      (node (ref "CN8") (pin "15") (pinfunction "15_15") (pintype "bidirectional"))
      (node (ref "U$3") (pin "49") (pinfunction "SDA3A/SDI3A/U3ARX/PMA9/CN17/RF4_49") (pintype "bidirectional"))
    )
    (net (code "77") (name "/U3ATX") (class "Default")
      (node (ref "CN8") (pin "13") (pinfunction "13_13") (pintype "bidirectional"))
      (node (ref "U$3") (pin "50") (pinfunction "SCL3A/SDO3A/U3ATX/PMA8/CN18/RF5_50") (pintype "bidirectional"))
    )
    (net (code "78") (name "/U3BRX") (class "Default")
      (node (ref "CN6") (pin "15") (pinfunction "15_15") (pintype "bidirectional"))
      (node (ref "U$3") (pin "40") (pinfunction "#SS3A/U3BRX/#U3ACTS/RF12_40") (pintype "bidirectional"))
    )
    (net (code "79") (name "/U3BTX") (class "Default")
      (node (ref "CN6") (pin "13") (pinfunction "13_13") (pintype "bidirectional"))
      (node (ref "U$3") (pin "39") (pinfunction "SCK3A/U3BTX/#U3ARTS/RF13_39") (pintype "bidirectional"))
    )
    (net (code "80") (name "/VBAT") (class "Default")
      (node (ref "C27") (pin "1") (pinfunction "1_1") (pintype "passive"))
      (node (ref "CN5") (pin "2") (pinfunction "1_2") (pintype "passive"))
      (node (ref "D3") (pin "ANODE") (pinfunction "ANODE_ANODE") (pintype "bidirectional"))
      (node (ref "U1") (pin "3") (pinfunction "VBAT_3") (pintype "power_in"))
    )
    (net (code "81") (name "/VIN") (class "Default")
      (node (ref "C1") (pin "1") (pinfunction "1_1") (pintype "passive"))
      (node (ref "C30") (pin "2") (pinfunction "2_2") (pintype "passive"))
      (node (ref "C35") (pin "1") (pinfunction "1_1") (pintype "passive"))
      (node (ref "CN4") (pin "3") (pinfunction "3_3") (pintype "bidirectional"))
      (node (ref "D2") (pin "CATHODE") (pinfunction "CATHODE_CATHODE") (pintype "bidirectional"))
      (node (ref "D3") (pin "CATHODE") (pinfunction "CATHODE_CATHODE") (pintype "bidirectional"))
      (node (ref "L1") (pin "2") (pinfunction "2_2") (pintype "bidirectional"))
      (node (ref "U$12") (pin "19") (pinfunction "VBAT_IN_19") (pintype "bidirectional"))
      (node (ref "U$2") (pin "5") (pinfunction "VIN_5") (pintype "bidirectional"))
      (node (ref "U$2") (pin "7") (pinfunction "PS/SYNC_7") (pintype "bidirectional"))
      (node (ref "U$2") (pin "8") (pinfunction "VINA_8") (pintype "bidirectional"))
      (node (ref "U$24") (pin "5") (pinfunction "VIN_5") (pintype "bidirectional"))
      (node (ref "U$5") (pin "P") (pinfunction "P_P") (pintype "passive"))
    )
    (net (code "82") (name "3.3V") (class "Default")
      (node (ref "C10") (pin "2") (pinfunction "2_2") (pintype "passive"))
      (node (ref "C11") (pin "2") (pinfunction "2_2") (pintype "passive"))
      (node (ref "C12") (pin "1") (pinfunction "1_1") (pintype "passive"))
      (node (ref "C13") (pin "1") (pinfunction "1_1") (pintype "passive"))
      (node (ref "C17") (pin "1") (pinfunction "1_1") (pintype "passive"))
      (node (ref "C18") (pin "2") (pinfunction "2_2") (pintype "passive"))
      (node (ref "C20") (pin "1") (pinfunction "1_1") (pintype "passive"))
      (node (ref "C21") (pin "1") (pinfunction "1_1") (pintype "passive"))
      (node (ref "C22") (pin "1") (pinfunction "1_1") (pintype "passive"))
      (node (ref "C28") (pin "1") (pinfunction "1_1") (pintype "passive"))
      (node (ref "C8") (pin "1") (pinfunction "1_1") (pintype "passive"))
      (node (ref "C9") (pin "1") (pinfunction "1_1") (pintype "passive"))
      (node (ref "CN1") (pin "17") (pinfunction "BS0_17") (pintype "bidirectional"))
      (node (ref "CN1") (pin "18") (pinfunction "BS1_18") (pintype "bidirectional"))
      (node (ref "CN1") (pin "27") (pinfunction "VCI_27") (pintype "bidirectional"))
      (node (ref "CN1") (pin "4") (pinfunction "VDDIO_4") (pintype "bidirectional"))
      (node (ref "CN2") (pin "2") (pinfunction "2_2") (pintype "bidirectional"))
      (node (ref "CN3") (pin "1") (pinfunction "1_1") (pintype "bidirectional"))
      (node (ref "CN4") (pin "5") (pinfunction "5_5") (pintype "bidirectional"))
      (node (ref "CN6") (pin "2") (pinfunction "2_2") (pintype "bidirectional"))
      (node (ref "CN7") (pin "2") (pinfunction "2_2") (pintype "bidirectional"))
      (node (ref "CN8") (pin "2") (pinfunction "2_2") (pintype "bidirectional"))
      (node (ref "CN9") (pin "2") (pinfunction "2_2") (pintype "bidirectional"))
      (node (ref "R10") (pin "1") (pinfunction "1_1") (pintype "passive"))
      (node (ref "R11") (pin "2") (pinfunction "2_2") (pintype "passive"))
      (node (ref "TP1") (pin "P$1") (pinfunction "1_P$1") (pintype "bidirectional"))
      (node (ref "TP2") (pin "P$1") (pinfunction "1_P$1") (pintype "bidirectional"))
      (node (ref "U$12") (pin "23") (pinfunction "VIO_23") (pintype "bidirectional"))
      (node (ref "U$15") (pin "5") (pinfunction "VCC_5") (pintype "bidirectional"))
      (node (ref "U$2") (pin "1") (pinfunction "VOUT_1") (pintype "bidirectional"))
      (node (ref "U$2") (pin "10") (pinfunction "FB_10") (pintype "bidirectional"))
      (node (ref "U$3") (pin "15") (pinfunction "VSS1_15") (pintype "bidirectional"))
      (node (ref "U$3") (pin "2") (pinfunction "VDD1_2") (pintype "bidirectional"))
      (node (ref "U$3") (pin "30") (pinfunction "AVDD_30") (pintype "bidirectional"))
      (node (ref "U$3") (pin "37") (pinfunction "VDD3_37") (pintype "bidirectional"))
      (node (ref "U$3") (pin "46") (pinfunction "VDD4_46") (pintype "bidirectional"))
      (node (ref "U$3") (pin "55") (pinfunction "VUSB_55") (pintype "bidirectional"))
      (node (ref "U$3") (pin "65") (pinfunction "VSS4_65") (pintype "bidirectional"))
      (node (ref "U$3") (pin "86") (pinfunction "VDD6_86") (pintype "bidirectional"))
      (node (ref "U$7") (pin "4") (pinfunction "VDD_4") (pintype "bidirectional"))
      (node (ref "U$9") (pin "1") (pinfunction "VCCIO_1") (pintype "power_in"))
    )
    (net (code "83") (name "5V") (class "Default")
      (node (ref "C48") (pin "1") (pinfunction "1_1") (pintype "passive"))
      (node (ref "D2") (pin "ANODE") (pinfunction "ANODE_ANODE") (pintype "bidirectional"))
      (node (ref "D4") (pin "ANODE") (pinfunction "ANODE_ANODE") (pintype "bidirectional"))
      (node (ref "D5") (pin "ANODE") (pinfunction "ANODE_ANODE") (pintype "bidirectional"))
      (node (ref "R13") (pin "2") (pinfunction "2_2") (pintype "passive"))
      (node (ref "R6") (pin "2") (pinfunction "2_2") (pintype "passive"))
      (node (ref "U$8") (pin "1") (pinfunction "VCC_1") (pintype "bidirectional"))
      (node (ref "U$9") (pin "19") (pinfunction "VCC_19") (pintype "power_in"))
      (node (ref "U1") (pin "4") (pinfunction "VIN_4") (pintype "power_in"))
    )
    (net (code "84") (name "GND") (class "Default")
      (node (ref "C1") (pin "2") (pinfunction "2_2") (pintype "passive"))
      (node (ref "C10") (pin "1") (pinfunction "1_1") (pintype "passive"))
      (node (ref "C11") (pin "1") (pinfunction "1_1") (pintype "passive"))
      (node (ref "C12") (pin "2") (pinfunction "2_2") (pintype "passive"))
      (node (ref "C13") (pin "2") (pinfunction "2_2") (pintype "passive"))
      (node (ref "C14") (pin "2") (pinfunction "2_2") (pintype "passive"))
      (node (ref "C15") (pin "2") (pinfunction "2_2") (pintype "passive"))
      (node (ref "C16") (pin "2") (pinfunction "2_2") (pintype "passive"))
      (node (ref "C17") (pin "2") (pinfunction "2_2") (pintype "passive"))
      (node (ref "C18") (pin "1") (pinfunction "1_1") (pintype "passive"))
      (node (ref "C19") (pin "2") (pinfunction "2_2") (pintype "passive"))
      (node (ref "C20") (pin "2") (pinfunction "2_2") (pintype "passive"))
      (node (ref "C21") (pin "2") (pinfunction "2_2") (pintype "passive"))
      (node (ref "C22") (pin "2") (pinfunction "2_2") (pintype "passive"))
      (node (ref "C27") (pin "2") (pinfunction "2_2") (pintype "passive"))
      (node (ref "C28") (pin "2") (pinfunction "2_2") (pintype "passive"))
      (node (ref "C30") (pin "1") (pinfunction "1_1") (pintype "passive"))
      (node (ref "C31") (pin "2") (pinfunction "2_2") (pintype "passive"))
      (node (ref "C35") (pin "2") (pinfunction "2_2") (pintype "passive"))
      (node (ref "C4") (pin "2") (pinfunction "2_2") (pintype "passive"))
      (node (ref "C48") (pin "2") (pinfunction "2_2") (pintype "passive"))
      (node (ref "C5") (pin "2") (pinfunction "2_2") (pintype "passive"))
      (node (ref "C6") (pin "2") (pinfunction "2_2") (pintype "passive"))
      (node (ref "C7") (pin "C") (pinfunction "-_C") (pintype "passive"))
      (node (ref "C8") (pin "2") (pinfunction "2_2") (pintype "passive"))
      (node (ref "C9") (pin "2") (pinfunction "2_2") (pintype "passive"))
      (node (ref "CN1") (pin "1") (pinfunction "GND1_1") (pintype "bidirectional"))
      (node (ref "CN1") (pin "28") (pinfunction "VSS_28") (pintype "bidirectional"))
      (node (ref "CN1") (pin "30") (pinfunction "GND2_30") (pintype "bidirectional"))
      (node (ref "CN1") (pin "PAD1") (pinfunction "PAD1_PAD1") (pintype "bidirectional"))
      (node (ref "CN1") (pin "PAD2") (pinfunction "PAD2_PAD2") (pintype "bidirectional"))
      (node (ref "CN2") (pin "3") (pinfunction "3_3") (pintype "bidirectional"))
      (node (ref "CN3") (pin "5") (pinfunction "5_5") (pintype "bidirectional"))
      (node (ref "CN4") (pin "1") (pinfunction "1_1") (pintype "bidirectional"))
      (node (ref "CN4") (pin "9") (pinfunction "9_9") (pintype "bidirectional"))
      (node (ref "CN4") (pin "PAD1") (pinfunction "PAD1_PAD1") (pintype "bidirectional"))
      (node (ref "CN4") (pin "PAD2") (pinfunction "PAD2_PAD2") (pintype "bidirectional"))
      (node (ref "CN5") (pin "1") (pinfunction "2_1") (pintype "passive"))
      (node (ref "CN6") (pin "1") (pinfunction "1_1") (pintype "bidirectional"))
      (node (ref "CN7") (pin "1") (pinfunction "1_1") (pintype "bidirectional"))
      (node (ref "CN8") (pin "1") (pinfunction "1_1") (pintype "bidirectional"))
      (node (ref "CN9") (pin "1") (pinfunction "1_1") (pintype "bidirectional"))
      (node (ref "D10") (pin "1") (pinfunction "CATHODE_1") (pintype "bidirectional"))
      (node (ref "R12") (pin "1") (pinfunction "1_1") (pintype "passive"))
      (node (ref "R14") (pin "1") (pinfunction "1_1") (pintype "passive"))
      (node (ref "R15") (pin "1") (pinfunction "1_1") (pintype "passive"))
      (node (ref "R19") (pin "1") (pinfunction "1_1") (pintype "passive"))
      (node (ref "R36") (pin "1") (pinfunction "1_1") (pintype "passive"))
      (node (ref "R7") (pin "1") (pinfunction "1_1") (pintype "passive"))
      (node (ref "R9") (pin "1") (pinfunction "1_1") (pintype "passive"))
      (node (ref "U$12") (pin "1") (pinfunction "GND_1") (pintype "bidirectional"))
      (node (ref "U$12") (pin "10") (pinfunction "GND_10") (pintype "bidirectional"))
      (node (ref "U$12") (pin "11") (pinfunction "GND_11") (pintype "bidirectional"))
      (node (ref "U$12") (pin "16") (pinfunction "GND_16") (pintype "bidirectional"))
      (node (ref "U$12") (pin "18") (pinfunction "GND_18") (pintype "bidirectional"))
      (node (ref "U$12") (pin "20") (pinfunction "GND_20") (pintype "bidirectional"))
      (node (ref "U$12") (pin "21") (pinfunction "EXT_32K_21") (pintype "bidirectional"))
      (node (ref "U$12") (pin "22") (pinfunction "GND_22") (pintype "bidirectional"))
      (node (ref "U$12") (pin "25") (pinfunction "GND_25") (pintype "bidirectional"))
      (node (ref "U$12") (pin "31") (pinfunction "GND_31") (pintype "bidirectional"))
      (node (ref "U$12") (pin "32") (pinfunction "GND_32") (pintype "bidirectional"))
      (node (ref "U$12") (pin "33") (pinfunction "GND_33") (pintype "bidirectional"))
      (node (ref "U$12") (pin "34") (pinfunction "GND_34") (pintype "bidirectional"))
      (node (ref "U$12") (pin "36") (pinfunction "GND_36") (pintype "bidirectional"))
      (node (ref "U$12") (pin "37") (pinfunction "GND_37") (pintype "bidirectional"))
      (node (ref "U$12") (pin "38") (pinfunction "GND_38") (pintype "bidirectional"))
      (node (ref "U$12") (pin "39") (pinfunction "GND_39") (pintype "bidirectional"))
      (node (ref "U$12") (pin "40") (pinfunction "GND_40") (pintype "bidirectional"))
      (node (ref "U$12") (pin "41") (pinfunction "GND_41") (pintype "bidirectional"))
      (node (ref "U$12") (pin "42") (pinfunction "GND_42") (pintype "bidirectional"))
      (node (ref "U$12") (pin "43") (pinfunction "GND_43") (pintype "bidirectional"))
      (node (ref "U$12") (pin "44") (pinfunction "GND_44") (pintype "bidirectional"))
      (node (ref "U$12") (pin "45") (pinfunction "GND_45") (pintype "bidirectional"))
      (node (ref "U$12") (pin "46") (pinfunction "GND_46") (pintype "bidirectional"))
      (node (ref "U$12") (pin "9") (pinfunction "GND_9") (pintype "bidirectional"))
      (node (ref "U$15") (pin "3") (pinfunction "GND_3") (pintype "bidirectional"))
      (node (ref "U$2") (pin "3") (pinfunction "PGND_3") (pintype "bidirectional"))
      (node (ref "U$2") (pin "9") (pinfunction "GND_9") (pintype "bidirectional"))
      (node (ref "U$2") (pin "TH1") (pinfunction "THERM1_TH1") (pintype "bidirectional"))
      (node (ref "U$2") (pin "TH2") (pinfunction "THERM2_TH2") (pintype "bidirectional"))
      (node (ref "U$2") (pin "TH3") (pinfunction "THERM3_TH3") (pintype "bidirectional"))
      (node (ref "U$2") (pin "TH4") (pinfunction "THERM4_TH4") (pintype "bidirectional"))
      (node (ref "U$24") (pin "2") (pinfunction "GND_2") (pintype "bidirectional"))
      (node (ref "U$3") (pin "16") (pinfunction "VDD2_16") (pintype "bidirectional"))
      (node (ref "U$3") (pin "31") (pinfunction "AVSS_31") (pintype "bidirectional"))
      (node (ref "U$3") (pin "36") (pinfunction "VSS2_36") (pintype "bidirectional"))
      (node (ref "U$3") (pin "45") (pinfunction "VSS3_45") (pintype "bidirectional"))
      (node (ref "U$3") (pin "62") (pinfunction "VDD5_62") (pintype "bidirectional"))
      (node (ref "U$3") (pin "75") (pinfunction "VSS5_75") (pintype "bidirectional"))
      (node (ref "U$7") (pin "6") (pinfunction "GND_6") (pintype "bidirectional"))
      (node (ref "U$7") (pin "9") (pinfunction "CDET1_9") (pintype "bidirectional"))
      (node (ref "U$8") (pin "5") (pinfunction "GND_5") (pintype "bidirectional"))
      (node (ref "U$8") (pin "S1") (pinfunction "SH1_S1") (pintype "bidirectional"))
      (node (ref "U$8") (pin "S2") (pinfunction "SH2_S2") (pintype "bidirectional"))
      (node (ref "U$8") (pin "S3") (pinfunction "SH3_S3") (pintype "bidirectional"))
      (node (ref "U$8") (pin "S4") (pinfunction "SH4_S4") (pintype "bidirectional"))
      (node (ref "U$9") (pin "17") (pinfunction "GND_17") (pintype "power_in"))
      (node (ref "U$9") (pin "20") (pinfunction "GND_20") (pintype "power_in"))
      (node (ref "U$9") (pin "24") (pinfunction "AGND_24") (pintype "power_in"))
      (node (ref "U$9") (pin "26") (pinfunction "TEST_26") (pintype "input"))
      (node (ref "U$9") (pin "4") (pinfunction "GND_4") (pintype "power_in"))
      (node (ref "U1") (pin "2") (pinfunction "VSS_2") (pintype "power_in"))
    )
    (net (code "85") (name "Net-(C3-Pad2)") (class "Default")
      (node (ref "C3") (pin "2") (pinfunction "2_2") (pintype "passive"))
      (node (ref "R3") (pin "2") (pinfunction "2_2") (pintype "passive"))
      (node (ref "SJ1") (pin "1") (pinfunction "1_1") (pintype "passive"))
    )
    (net (code "86") (name "Net-(C7-+)") (class "Default")
      (node (ref "C7") (pin "A") (pinfunction "+_A") (pintype "passive"))
      (node (ref "U$3") (pin "85") (pinfunction "VCAP/VDDCORE_85") (pintype "bidirectional"))
    )
    (net (code "87") (name "Net-(C31-Pad1)") (class "Default")
      (node (ref "C31") (pin "1") (pinfunction "1_1") (pintype "passive"))
      (node (ref "L6") (pin "2") (pinfunction "2_2") (pintype "passive"))
      (node (ref "U$6") (pin "1") (pinfunction "1_1") (pintype "bidirectional"))
    )
    (net (code "88") (name "Net-(CN1-IREF)") (class "Default")
      (node (ref "CN1") (pin "22") (pinfunction "IREF_22") (pintype "bidirectional"))
      (node (ref "R15") (pin "2") (pinfunction "2_2") (pintype "passive"))
    )
    (net (code "89") (name "Net-(CN1-VCOMH)") (class "Default")
      (node (ref "C15") (pin "1") (pinfunction "1_1") (pintype "passive"))
      (node (ref "CN1") (pin "3") (pinfunction "VCOMH_3") (pintype "bidirectional"))
    )
    (net (code "90") (name "Net-(CN1-VDD)") (class "Default")
      (node (ref "C16") (pin "1") (pinfunction "1_1") (pintype "passive"))
      (node (ref "CN1") (pin "26") (pinfunction "VDD_26") (pintype "bidirectional"))
    )
    (net (code "91") (name "Net-(CN1-VSL)") (class "Default")
      (node (ref "CN1") (pin "5") (pinfunction "VSL_5") (pintype "bidirectional"))
      (node (ref "R18") (pin "2") (pinfunction "2_2") (pintype "passive"))
    )
    (net (code "92") (name "Net-(D4-PadCATHODE)") (class "Default")
      (node (ref "D4") (pin "CATHODE") (pinfunction "CATHODE_CATHODE") (pintype "bidirectional"))
      (node (ref "R1") (pin "2") (pinfunction "2_2") (pintype "passive"))
    )
    (net (code "93") (name "Net-(D5-PadCATHODE)") (class "Default")
      (node (ref "D5") (pin "CATHODE") (pinfunction "CATHODE_CATHODE") (pintype "bidirectional"))
      (node (ref "R2") (pin "2") (pinfunction "2_2") (pintype "passive"))
    )
    (net (code "94") (name "Net-(D8-ANODE)") (class "Default")
      (node (ref "D8") (pin "2") (pinfunction "ANODE_2") (pintype "bidirectional"))
      (node (ref "L1") (pin "1") (pinfunction "1_1") (pintype "bidirectional"))
      (node (ref "U$24") (pin "1") (pinfunction "SW_1") (pintype "bidirectional"))
    )
    (net (code "95") (name "Net-(D9-ANODE)") (class "Default")
      (node (ref "D9") (pin "2") (pinfunction "ANODE_2") (pintype "bidirectional"))
      (node (ref "R18") (pin "1") (pinfunction "1_1") (pintype "passive"))
    )
    (net (code "96") (name "Net-(D10-ANODE)") (class "Default")
      (node (ref "D10") (pin "2") (pinfunction "ANODE_2") (pintype "bidirectional"))
      (node (ref "D9") (pin "1") (pinfunction "CATHODE_1") (pintype "bidirectional"))
    )
    (net (code "97") (name "Net-(U$2-L1)") (class "Default")
      (node (ref "L3") (pin "1") (pinfunction "1_1") (pintype "bidirectional"))
      (node (ref "U$2") (pin "4") (pinfunction "L1_4") (pintype "bidirectional"))
    )
    (net (code "98") (name "Net-(U$2-L2)") (class "Default")
      (node (ref "L3") (pin "2") (pinfunction "2_2") (pintype "bidirectional"))
      (node (ref "U$2") (pin "2") (pinfunction "L2_2") (pintype "bidirectional"))
    )
    (net (code "99") (name "Net-(U$8-D+)") (class "Default")
      (node (ref "U$8") (pin "3") (pinfunction "D+_3") (pintype "bidirectional"))
      (node (ref "U$9") (pin "14") (pinfunction "USBDP_14") (pintype "bidirectional"))
    )
    (net (code "100") (name "Net-(U$8-D-)") (class "Default")
      (node (ref "U$8") (pin "2") (pinfunction "D-_2") (pintype "bidirectional"))
      (node (ref "U$9") (pin "15") (pinfunction "USBDM_15") (pintype "bidirectional"))
    )
    (net (code "101") (name "Net-(U$9-DTR)") (class "Default")
      (node (ref "C3") (pin "1") (pinfunction "1_1") (pintype "passive"))
      (node (ref "U$9") (pin "31") (pinfunction "DTR_31") (pintype "output"))
    )
    (net (code "102") (name "Net-(U$9-RESET)") (class "Default")
      (node (ref "C4") (pin "1") (pinfunction "1_1") (pintype "passive"))
      (node (ref "R6") (pin "1") (pinfunction "1_1") (pintype "passive"))
      (node (ref "R7") (pin "2") (pinfunction "2_2") (pintype "passive"))
      (node (ref "U$9") (pin "18") (pinfunction "RESET_18") (pintype "input"))
    )
    (net (code "103") (name "Net-(U$9-RTS)") (class "Default")
      (node (ref "R3") (pin "1") (pinfunction "1_1") (pintype "passive"))
      (node (ref "U$9") (pin "32") (pinfunction "RTS_32") (pintype "output"))
    )
    (net (code "104") (name "Net-(U$9-RXD)") (class "Default")
      (node (ref "R5") (pin "1") (pinfunction "1_1") (pintype "passive"))
      (node (ref "U$9") (pin "2") (pinfunction "RXD_2") (pintype "input"))
    )
    (net (code "105") (name "Net-(U$9-RXLED)") (class "Default")
      (node (ref "R2") (pin "1") (pinfunction "1_1") (pintype "passive"))
      (node (ref "U$9") (pin "21") (pinfunction "RXLED_21") (pintype "input"))
    )
    (net (code "106") (name "Net-(U$9-TXD)") (class "Default")
      (node (ref "R4") (pin "1") (pinfunction "1_1") (pintype "passive"))
      (node (ref "U$9") (pin "30") (pinfunction "TXD_30") (pintype "output"))
    )
    (net (code "107") (name "Net-(U$9-TXLED)") (class "Default")
      (node (ref "R1") (pin "1") (pinfunction "1_1") (pintype "passive"))
      (node (ref "U$9") (pin "22") (pinfunction "TXLED_22") (pintype "input"))
    )
    (net (code "108") (name "Net-(U$12-RF_ANT)") (class "Default")
      (node (ref "L6") (pin "1") (pinfunction "1_1") (pintype "passive"))
      (node (ref "U$12") (pin "35") (pinfunction "RF_ANT_35") (pintype "bidirectional"))
    )
    (net (code "109") (name "Net-(U$12-SCL_CC3000)") (class "Default")
      (node (ref "U$12") (pin "29") (pinfunction "SCL_EEPROM_29") (pintype "bidirectional"))
      (node (ref "U$12") (pin "30") (pinfunction "SCL_CC3000_30") (pintype "bidirectional"))
    )
    (net (code "110") (name "Net-(U$12-SDA_CC3000)") (class "Default")
      (node (ref "U$12") (pin "27") (pinfunction "SDA_EEPROM_27") (pintype "bidirectional"))
      (node (ref "U$12") (pin "28") (pinfunction "SDA_CC3000_28") (pintype "bidirectional"))
    )
    (net (code "111") (name "Net-(U$12-WL_EN1)") (class "Default")
      (node (ref "U$12") (pin "5") (pinfunction "WL_EN2_5") (pintype "bidirectional"))
      (node (ref "U$12") (pin "7") (pinfunction "WL_EN1_7") (pintype "bidirectional"))
    )
    (net (code "112") (name "Net-(U$24-FB)") (class "Default")
      (node (ref "C2") (pin "2") (pinfunction "2_2") (pintype "passive"))
      (node (ref "R8") (pin "1") (pinfunction "1_1") (pintype "passive"))
      (node (ref "R9") (pin "2") (pinfunction "2_2") (pintype "passive"))
      (node (ref "U$24") (pin "3") (pinfunction "FB_3") (pintype "bidirectional"))
    )
    (net (code "113") (name "Net-(U1-PROG)") (class "Default")
      (node (ref "R12") (pin "2") (pinfunction "2_2") (pintype "passive"))
      (node (ref "U1") (pin "5") (pinfunction "PROG_5") (pintype "input"))
    )
    (net (code "114") (name "Net-(U1-STAT)") (class "Default")
      (node (ref "D1") (pin "CATHODE") (pinfunction "CATHODE_CATHODE") (pintype "bidirectional"))
      (node (ref "U1") (pin "1") (pinfunction "STAT_1") (pintype "output"))
    )
    (net (code "115") (name "unconnected-(CN1-GPIO0-Pad24)") (class "Default")
      (node (ref "CN1") (pin "24") (pinfunction "GPIO0_24") (pintype "bidirectional"))
    )
    (net (code "116") (name "unconnected-(CN1-GPIO1-Pad23)") (class "Default")
      (node (ref "CN1") (pin "23") (pinfunction "GPIO1_23") (pintype "bidirectional"))
    )
    (net (code "117") (name "unconnected-(CN4-Pad7)") (class "Default")
      (node (ref "CN4") (pin "7") (pinfunction "7_7") (pintype "bidirectional"))
    )
    (net (code "118") (name "unconnected-(CN7-Pad13)") (class "Default")
      (node (ref "CN7") (pin "13") (pinfunction "13_13") (pintype "bidirectional"))
    )
    (net (code "119") (name "unconnected-(CN7-Pad15)") (class "Default")
      (node (ref "CN7") (pin "15") (pinfunction "15_15") (pintype "bidirectional"))
    )
    (net (code "120") (name "unconnected-(U$3-#SS1{slash}IC2{slash}RD9-Pad69)") (class "Default")
      (node (ref "U$3") (pin "69") (pinfunction "#SS1/IC2/RD9_69") (pintype "bidirectional"))
    )
    (net (code "121") (name "unconnected-(U$3-ETXCLK{slash}PMD15{slash}CN16{slash}RD7-Pad84)") (class "Default")
      (node (ref "U$3") (pin "84") (pinfunction "ETXCLK/PMD15/CN16/RD7_84") (pintype "bidirectional"))
    )
    (net (code "122") (name "unconnected-(U$3-ETXD3{slash}PMD13{slash}CN19{slash}RD13-Pad80)") (class "Default")
      (node (ref "U$3") (pin "80") (pinfunction "ETXD3/PMD13/CN19/RD13_80") (pintype "bidirectional"))
    )
    (net (code "123") (name "unconnected-(U$3-SCL2{slash}RA2-Pad58)") (class "Default")
      (node (ref "U$3") (pin "58") (pinfunction "SCL2/RA2_58") (pintype "bidirectional"))
    )
    (net (code "124") (name "unconnected-(U$3-SDA2{slash}RA3-Pad59)") (class "Default")
      (node (ref "U$3") (pin "59") (pinfunction "SDA2/RA3_59") (pintype "bidirectional"))
    )
    (net (code "125") (name "unconnected-(U$3-T2CK{slash}RC1-Pad6)") (class "Default")
      (node (ref "U$3") (pin "6") (pinfunction "T2CK/RC1_6") (pintype "bidirectional"))
    )
    (net (code "126") (name "unconnected-(U$3-TCK{slash}RA1-Pad38)") (class "Default")
      (node (ref "U$3") (pin "38") (pinfunction "TCK/RA1_38") (pintype "bidirectional"))
    )
    (net (code "127") (name "unconnected-(U$3-VBUS-Pad54)") (class "Default")
      (node (ref "U$3") (pin "54") (pinfunction "VBUS_54") (pintype "bidirectional"))
    )
    (net (code "128") (name "unconnected-(U$3-VREF+{slash}CVREF+{slash}AERXD3{slash}PMA6{slash}RA10-Pad29)") (class "Default")
      (node (ref "U$3") (pin "29") (pinfunction "VREF+/CVREF+/AERXD3/PMA6/RA10_29") (pintype "bidirectional"))
    )
    (net (code "129") (name "unconnected-(U$3-VREF-{slash}CVREF-{slash}AERXD2{slash}PMA7{slash}RA9-Pad28)") (class "Default")
      (node (ref "U$3") (pin "28") (pinfunction "VREF-/CVREF-/AERXD2/PMA7/RA9_28") (pintype "bidirectional"))
    )
    (net (code "130") (name "unconnected-(U$5-PadS)") (class "Default")
      (node (ref "U$5") (pin "S") (pinfunction "S_S") (pintype "passive"))
    )
    (net (code "131") (name "unconnected-(U$7-DAT1-Pad8)") (class "Default")
      (node (ref "U$7") (pin "8") (pinfunction "DAT1_8") (pintype "bidirectional"))
    )
    (net (code "132") (name "unconnected-(U$7-DAT2-Pad1)") (class "Default")
      (node (ref "U$7") (pin "1") (pinfunction "DAT2_1") (pintype "bidirectional"))
    )
    (net (code "133") (name "unconnected-(U$8-ID-Pad4)") (class "Default")
      (node (ref "U$8") (pin "4") (pinfunction "ID_4") (pintype "bidirectional"))
    )
    (net (code "134") (name "unconnected-(U$9-3V3OUT-Pad16)") (class "Default")
      (node (ref "U$9") (pin "16") (pinfunction "3V3OUT_16") (pintype "output"))
    )
    (net (code "135") (name "unconnected-(U$9-CTS-Pad8)") (class "Default")
      (node (ref "U$9") (pin "8") (pinfunction "CTS_8") (pintype "input"))
    )
    (net (code "136") (name "unconnected-(U$9-DCD-Pad7)") (class "Default")
      (node (ref "U$9") (pin "7") (pinfunction "DCD_7") (pintype "input"))
    )
    (net (code "137") (name "unconnected-(U$9-DSR-Pad6)") (class "Default")
      (node (ref "U$9") (pin "6") (pinfunction "DSR_6") (pintype "input"))
    )
    (net (code "138") (name "unconnected-(U$9-OSCI-Pad27)") (class "Default")
      (node (ref "U$9") (pin "27") (pinfunction "OSCI_27") (pintype "input"))
    )
    (net (code "139") (name "unconnected-(U$9-OSCO-Pad28)") (class "Default")
      (node (ref "U$9") (pin "28") (pinfunction "OSCO_28") (pintype "output"))
    )
    (net (code "140") (name "unconnected-(U$9-PWREN-Pad11)") (class "Default")
      (node (ref "U$9") (pin "11") (pinfunction "PWREN_11") (pintype "input"))
    )
    (net (code "141") (name "unconnected-(U$9-RI-Pad3)") (class "Default")
      (node (ref "U$9") (pin "3") (pinfunction "RI_3") (pintype "input"))
    )
    (net (code "142") (name "unconnected-(U$9-SLEEP-Pad9)") (class "Default")
      (node (ref "U$9") (pin "9") (pinfunction "SLEEP_9") (pintype "input"))
    )
    (net (code "143") (name "unconnected-(U$9-TXDEN-Pad10)") (class "Default")
      (node (ref "U$9") (pin "10") (pinfunction "TXDEN_10") (pintype "input"))
    )
    (net (code "144") (name "unconnected-(U$12-RESV1-Pad2)") (class "Default")
      (node (ref "U$12") (pin "2") (pinfunction "RESV1_2") (pintype "bidirectional"))
    )
    (net (code "145") (name "unconnected-(U$12-RESV2-Pad4)") (class "Default")
      (node (ref "U$12") (pin "4") (pinfunction "RESV2_4") (pintype "bidirectional"))
    )
    (net (code "146") (name "unconnected-(U$12-RESV3-Pad24)") (class "Default")
      (node (ref "U$12") (pin "24") (pinfunction "RESV3_24") (pintype "bidirectional"))
    )
    (net (code "147") (name "unconnected-(U$12-WL_RS232_RX-Pad8)") (class "Default")
      (node (ref "U$12") (pin "8") (pinfunction "WL_RS232_RX_8") (pintype "bidirectional"))
    )
    (net (code "148") (name "unconnected-(U$12-WL_RS232_TX-Pad6)") (class "Default")
      (node (ref "U$12") (pin "6") (pinfunction "WL_RS232_TX_6") (pintype "bidirectional"))
    )
  )
)
